# fonte-diagrama.net
KiCad netlist of a schematic drawn in EAGLE
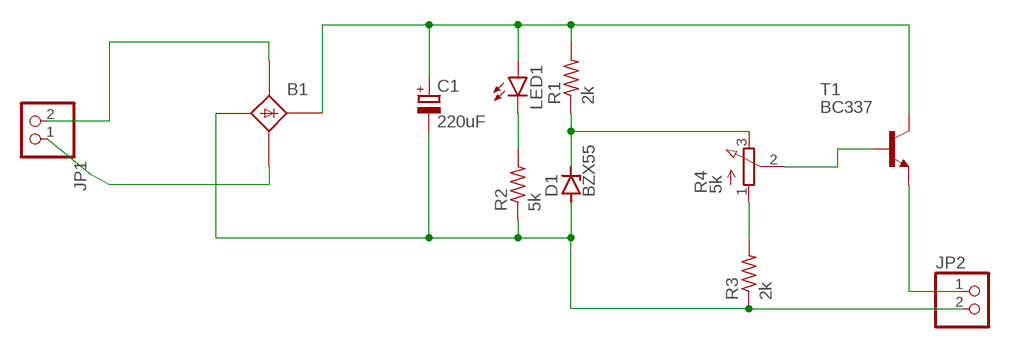
[diagram p0: schematic, sheet 1]

(export (version "E")
  (design (tool "Eeschema 10.0.6"))
  (components
    (comp (ref "B1")
      (value "B25A-")
      (footprint "eagle-import:B25A-")
      (fields (field (name "SPICEPREFIX") "X"))
      (libsource (lib "eagle-import") (part "B25A-"))
    )
    (comp (ref "C1")
      (value "220uF")
      (footprint "eagle-import:EB20D")
      (libsource (lib "eagle-import") (part "CPOL-EUE10-20"))
    )
    (comp (ref "D1")
      (value "BZX55")
      (footprint "eagle-import:DO35Z10")
      (libsource (lib "eagle-import") (part "BZX55"))
    )
    (comp (ref "JP1")
      (value "PINHD-1X2")
      (footprint "eagle-import:1X02")
      (libsource (lib "eagle-import") (part "PINHD-1X2"))
    )
    (comp (ref "JP2")
      (value "PINHD-1X2")
      (footprint "eagle-import:1X02")
      (libsource (lib "eagle-import") (part "PINHD-1X2"))
    )
    (comp (ref "LED1")
      (value "LED5MM")
      (footprint "eagle-import:LED5MM")
      (libsource (lib "eagle-import") (part "LED5MM"))
    )
    (comp (ref "R1")
      (value "2k")
      (footprint "eagle-import:0207_10")
      (libsource (lib "eagle-import") (part "R-US_0207/10"))
    )
    (comp (ref "R2")
      (value "5k")
      (footprint "eagle-import:0207_10")
      (libsource (lib "eagle-import") (part "R-US_0207/10"))
    )
    (comp (ref "R3")
      (value "2k")
      (footprint "eagle-import:0207_10")
      (libsource (lib "eagle-import") (part "R-US_0207/10"))
    )
    (comp (ref "R4")
      (value "5k")
      (footprint "eagle-import:3RP_1610N")
      (libsource (lib "eagle-import") (part "3RP/1610N"))
    )
    (comp (ref "T1")
      (value "BC337")
      (footprint "eagle-import:TO92")
      (libsource (lib "eagle-import") (part "BC337"))
    )
  )
  (nets
    (net (code "1") (name "Net-(B1---Pad-1)") (class "Default")
      (node (ref "B1") (pin "-1") (pinfunction "-_-1") (pintype "passive"))
      (node (ref "C1") (pin "-") (pinfunction "-_-") (pintype "passive"))
      (node (ref "D1") (pin "A") (pinfunction "A_A") (pintype "passive"))
      (node (ref "JP2") (pin "2") (pinfunction "2_2") (pintype "passive"))
      (node (ref "R2") (pin "1") (pinfunction "1_1") (pintype "passive"))
      (node (ref "R3") (pin "1") (pinfunction "1_1") (pintype "passive"))
    )
    (net (code "2") (name "Net-(B1-AC1-PadAC1-)") (class "Default")
      (node (ref "B1") (pin "AC1-") (pinfunction "AC1_AC1-") (pintype "passive"))
      (node (ref "JP1") (pin "2") (pinfunction "2_2") (pintype "passive"))
    )
    (net (code "3") (name "Net-(B1-AC2-PadAC2-)") (class "Default")
      (node (ref "B1") (pin "AC2-") (pinfunction "AC2_AC2-") (pintype "passive"))
      (node (ref "JP1") (pin "1") (pinfunction "1_1") (pintype "passive"))
    )
    (net (code "4") (name "Net-(LED1-C)") (class "Default")
      (node (ref "LED1") (pin "K") (pinfunction "C_K") (pintype "passive"))
      (node (ref "R2") (pin "2") (pinfunction "2_2") (pintype "passive"))
    )
    (net (code "5") (name "Net-(R4-A)") (class "Default")
      (node (ref "R3") (pin "2") (pinfunction "2_2") (pintype "passive"))
      (node (ref "R4") (pin "1") (pinfunction "A_1") (pintype "passive"))
    )
    (net (code "6") (name "Net-(R4-E)") (class "Default")
      (node (ref "D1") (pin "C") (pinfunction "C_C") (pintype "passive"))
      (node (ref "R1") (pin "1") (pinfunction "1_1") (pintype "passive"))
      (node (ref "R4") (pin "3") (pinfunction "E_3") (pintype "passive"))
    )
    (net (code "7") (name "Net-(R4-S)") (class "Default")
      (node (ref "R4") (pin "2") (pinfunction "S_2") (pintype "passive"))
      (node (ref "T1") (pin "2") (pinfunction "B_2") (pintype "passive"))
    )
    (net (code "8") (name "Net-(T1-C)") (class "Default")
      (node (ref "B1") (pin "+1") (pinfunction "+_+1") (pintype "passive"))
      (node (ref "C1") (pin "+") (pinfunction "+_+") (pintype "passive"))
      (node (ref "LED1") (pin "A") (pinfunction "A_A") (pintype "passive"))
      (node (ref "R1") (pin "2") (pinfunction "2_2") (pintype "passive"))
      (node (ref "T1") (pin "3") (pinfunction "C_3") (pintype "passive"))
    )
    (net (code "9") (name "Net-(T1-E)") (class "Default")
      (node (ref "JP2") (pin "1") (pinfunction "1_1") (pintype "passive"))
      (node (ref "T1") (pin "1") (pinfunction "E_1") (pintype "passive"))
    )
    (net (code "10") (name "unconnected-(B1-Pad+)") (class "Default")
      (node (ref "B1") (pin "+") (pinfunction "+_+") (pintype "passive"))
    )
    (net (code "11") (name "unconnected-(B1-Pad-)") (class "Default")
      (node (ref "B1") (pin "-") (pinfunction "-_-") (pintype "passive"))
    )
    (net (code "12") (name "unconnected-(B1-PadAC1)") (class "Default")
      (node (ref "B1") (pin "AC1") (pinfunction "AC1_AC1") (pintype "passive"))
    )
    (net (code "13") (name "unconnected-(B1-PadAC2)") (class "Default")
      (node (ref "B1") (pin "AC2") (pinfunction "AC2_AC2") (pintype "passive"))
    )
  )
)
